# LoRaBB.net
KiCad netlist of a schematic drawn in EAGLE
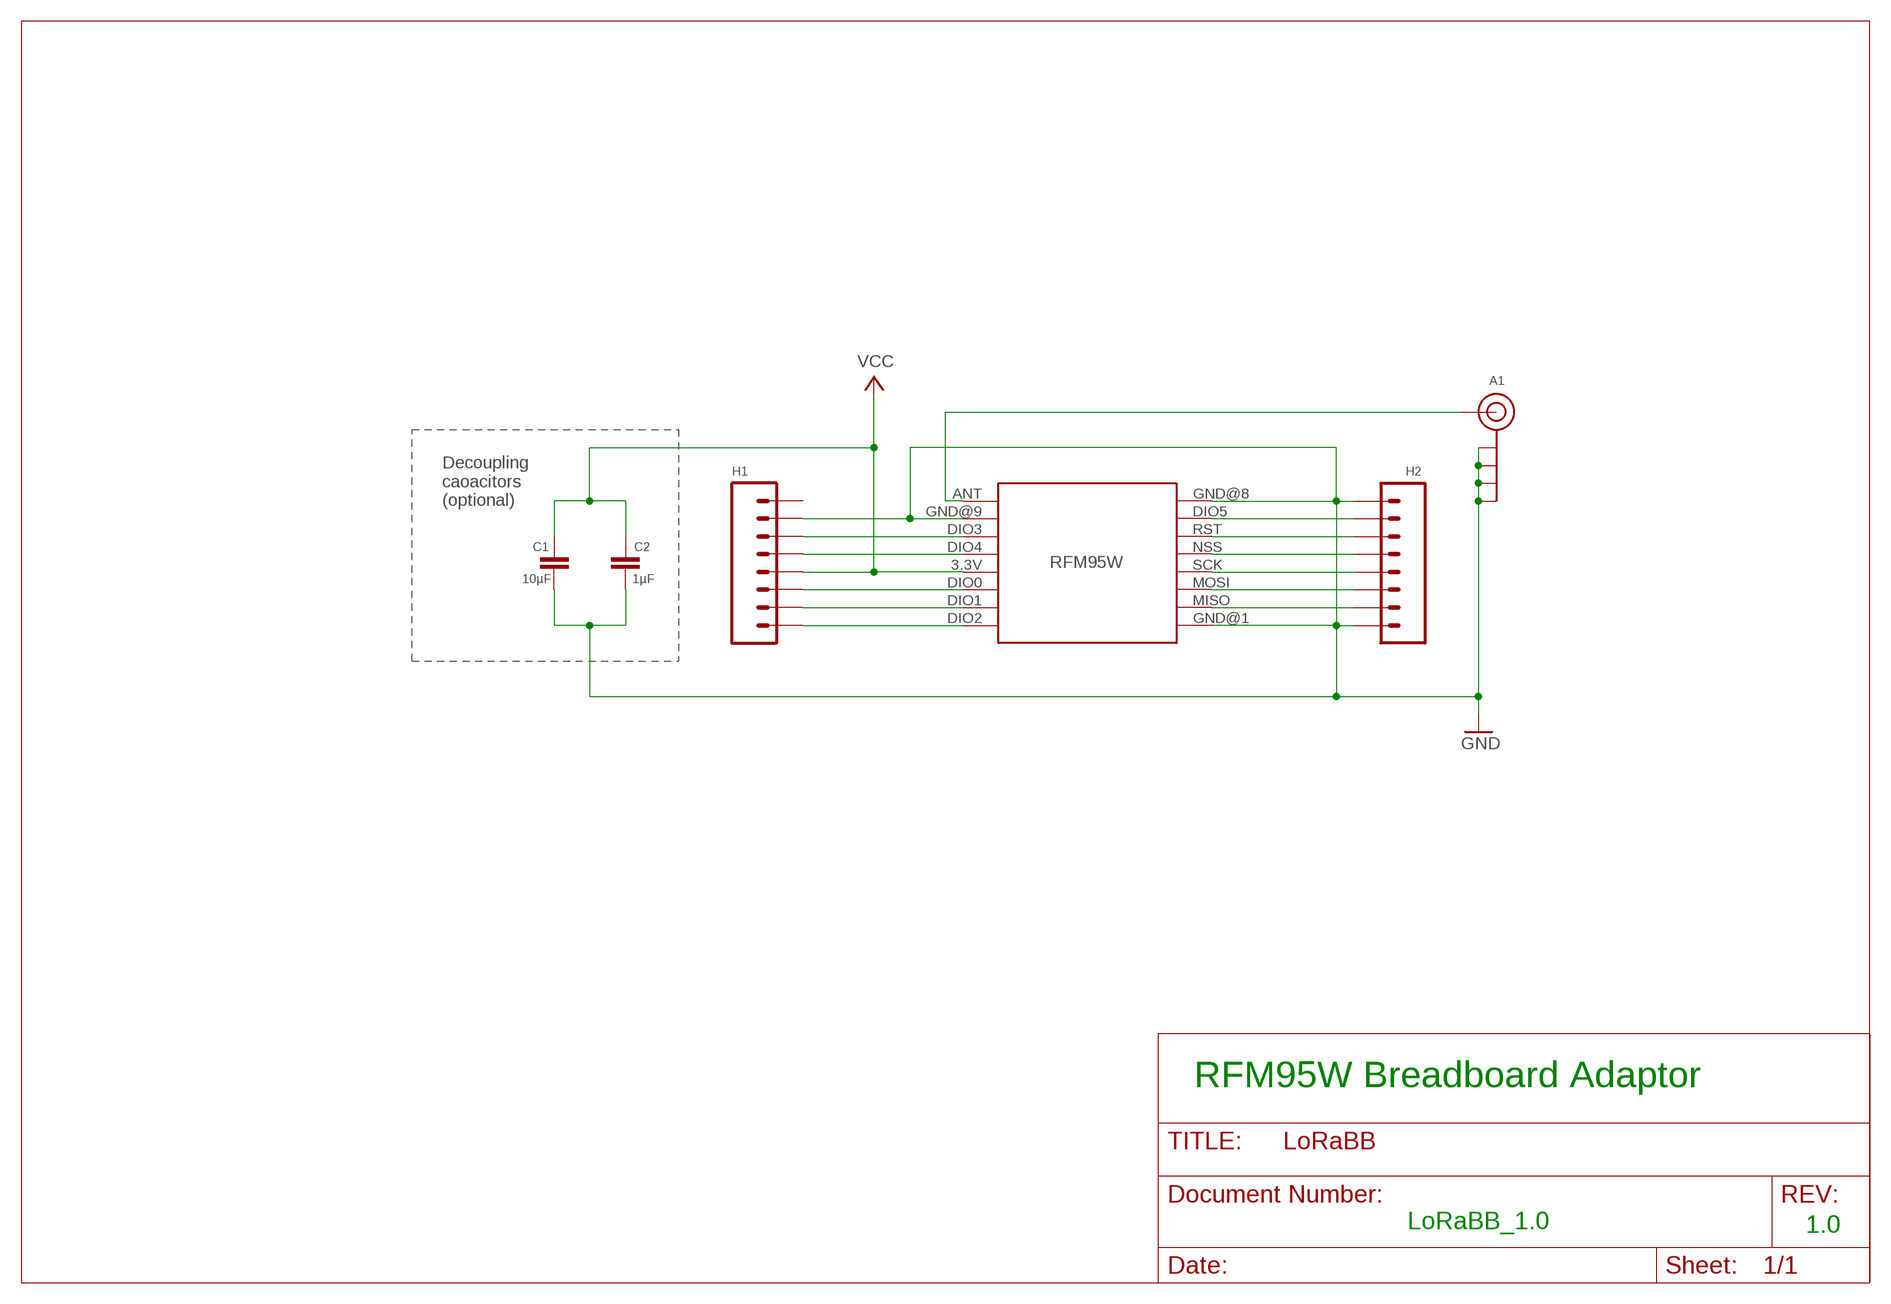
[diagram p0: schematic, sheet 1]

(export (version "E")
  (design (tool "Eeschema 10.0.6"))
  (components
    (comp (ref "A1")
      (value "U.FL-SMA-EDGE-COMBO")
      (footprint "eagle-import:U.FL-SMA-EDGE-COMBO")
      (libsource (lib "eagle-import") (part "U.FL-SMA-EDGE-COMBO"))
    )
    (comp (ref "C1")
      (value "10µF")
      (footprint "eagle-import:C0805")
      (libsource (lib "eagle-import") (part "CAPACITOR"))
    )
    (comp (ref "C2")
      (value "1µF")
      (footprint "eagle-import:C0805")
      (libsource (lib "eagle-import") (part "CAPACITOR"))
    )
    (comp (ref "H1")
      (value "1X8-PIN-HEADER")
      (footprint "eagle-import:1X8")
      (libsource (lib "eagle-import") (part "1X8-PIN-HEADER"))
    )
    (comp (ref "H2")
      (value "1X8-PIN-HEADER")
      (footprint "eagle-import:1X8")
      (libsource (lib "eagle-import") (part "1X8-PIN-HEADER"))
    )
    (comp (ref "RFM95W")
      (value "RFM95W-LORA")
      (footprint "eagle-import:RFM95W-LORA")
      (libsource (lib "eagle-import") (part "RFM95W-LORA"))
    )
  )
  (nets
    (net (code "1") (name "GND") (class "Default")
      (node (ref "A1") (pin "GND@1A") (pinfunction "GND_GND@1A") (pintype "bidirectional"))
      (node (ref "A1") (pin "GND@1B") (pinfunction "GND_GND@1B") (pintype "bidirectional"))
      (node (ref "A1") (pin "GND@2A") (pinfunction "GND_GND@2A") (pintype "bidirectional"))
      (node (ref "A1") (pin "GND@2B") (pinfunction "GND_GND@2B") (pintype "bidirectional"))
      (node (ref "C1") (pin "2") (pinfunction "2_2") (pintype "passive"))
      (node (ref "C2") (pin "2") (pinfunction "2_2") (pintype "passive"))
      (node (ref "H1") (pin "2") (pinfunction "2_2") (pintype "passive"))
      (node (ref "H2") (pin "1") (pinfunction "1_1") (pintype "passive"))
      (node (ref "H2") (pin "8") (pinfunction "8_8") (pintype "passive"))
      (node (ref "RFM95W") (pin "GND@1") (pinfunction "GND.1_GND@1") (pintype "power_in"))
      (node (ref "RFM95W") (pin "GND@8") (pinfunction "GND.2_GND@8") (pintype "power_in"))
      (node (ref "RFM95W") (pin "GND@9") (pinfunction "GND.3_GND@9") (pintype "power_in"))
    )
    (net (code "2") (name "Net-(A1-PadSIG)") (class "Default")
      (node (ref "A1") (pin "SIG") (pinfunction "SIG_SIG") (pintype "bidirectional"))
      (node (ref "RFM95W") (pin "ANT") (pinfunction "ANT_ANT") (pintype "passive"))
    )
    (net (code "3") (name "Net-(H1-Pad3)") (class "Default")
      (node (ref "H1") (pin "3") (pinfunction "3_3") (pintype "passive"))
      (node (ref "RFM95W") (pin "DIO3") (pinfunction "DIO3_DIO3") (pintype "bidirectional"))
    )
    (net (code "4") (name "Net-(H1-Pad4)") (class "Default")
      (node (ref "H1") (pin "4") (pinfunction "4_4") (pintype "passive"))
      (node (ref "RFM95W") (pin "DIO4") (pinfunction "DIO4_DIO4") (pintype "bidirectional"))
    )
    (net (code "5") (name "Net-(H1-Pad6)") (class "Default")
      (node (ref "H1") (pin "6") (pinfunction "6_6") (pintype "passive"))
      (node (ref "RFM95W") (pin "DIO0") (pinfunction "DIO0_DIO0") (pintype "bidirectional"))
    )
    (net (code "6") (name "Net-(H1-Pad7)") (class "Default")
      (node (ref "H1") (pin "7") (pinfunction "7_7") (pintype "passive"))
      (node (ref "RFM95W") (pin "DIO1") (pinfunction "DIO1_DIO1") (pintype "bidirectional"))
    )
    (net (code "7") (name "Net-(H1-Pad8)") (class "Default")
      (node (ref "H1") (pin "8") (pinfunction "8_8") (pintype "passive"))
      (node (ref "RFM95W") (pin "DIO2") (pinfunction "DIO2_DIO2") (pintype "bidirectional"))
    )
    (net (code "8") (name "Net-(H2-Pad2)") (class "Default")
      (node (ref "H2") (pin "2") (pinfunction "2_2") (pintype "passive"))
      (node (ref "RFM95W") (pin "DIO5") (pinfunction "DIO5_DIO5") (pintype "bidirectional"))
    )
    (net (code "9") (name "Net-(H2-Pad3)") (class "Default")
      (node (ref "H2") (pin "3") (pinfunction "3_3") (pintype "passive"))
      (node (ref "RFM95W") (pin "RST") (pinfunction "RST_RST") (pintype "bidirectional"))
    )
    (net (code "10") (name "Net-(H2-Pad4)") (class "Default")
      (node (ref "H2") (pin "4") (pinfunction "4_4") (pintype "passive"))
      (node (ref "RFM95W") (pin "NSS") (pinfunction "NSS_NSS") (pintype "bidirectional"))
    )
    (net (code "11") (name "Net-(H2-Pad5)") (class "Default")
      (node (ref "H2") (pin "5") (pinfunction "5_5") (pintype "passive"))
      (node (ref "RFM95W") (pin "SCK") (pinfunction "SCK_SCK") (pintype "bidirectional"))
    )
    (net (code "12") (name "Net-(H2-Pad6)") (class "Default")
      (node (ref "H2") (pin "6") (pinfunction "6_6") (pintype "passive"))
      (node (ref "RFM95W") (pin "MOSI") (pinfunction "MOSI_MOSI") (pintype "bidirectional"))
    )
    (net (code "13") (name "Net-(H2-Pad7)") (class "Default")
      (node (ref "H2") (pin "7") (pinfunction "7_7") (pintype "passive"))
      (node (ref "RFM95W") (pin "MISO") (pinfunction "MISO_MISO") (pintype "bidirectional"))
    )
    (net (code "14") (name "VCC") (class "Default")
      (node (ref "C1") (pin "1") (pinfunction "1_1") (pintype "passive"))
      (node (ref "C2") (pin "1") (pinfunction "1_1") (pintype "passive"))
      (node (ref "H1") (pin "5") (pinfunction "5_5") (pintype "passive"))
      (node (ref "RFM95W") (pin "3.3V") (pinfunction "3.3V_3.3V") (pintype "power_in"))
    )
    (net (code "15") (name "unconnected-(H1-Pad1)") (class "Default")
      (node (ref "H1") (pin "1") (pinfunction "1_1") (pintype "passive"))
    )
  )
)
